# pov.net
KiCad netlist of a schematic drawn in EAGLE
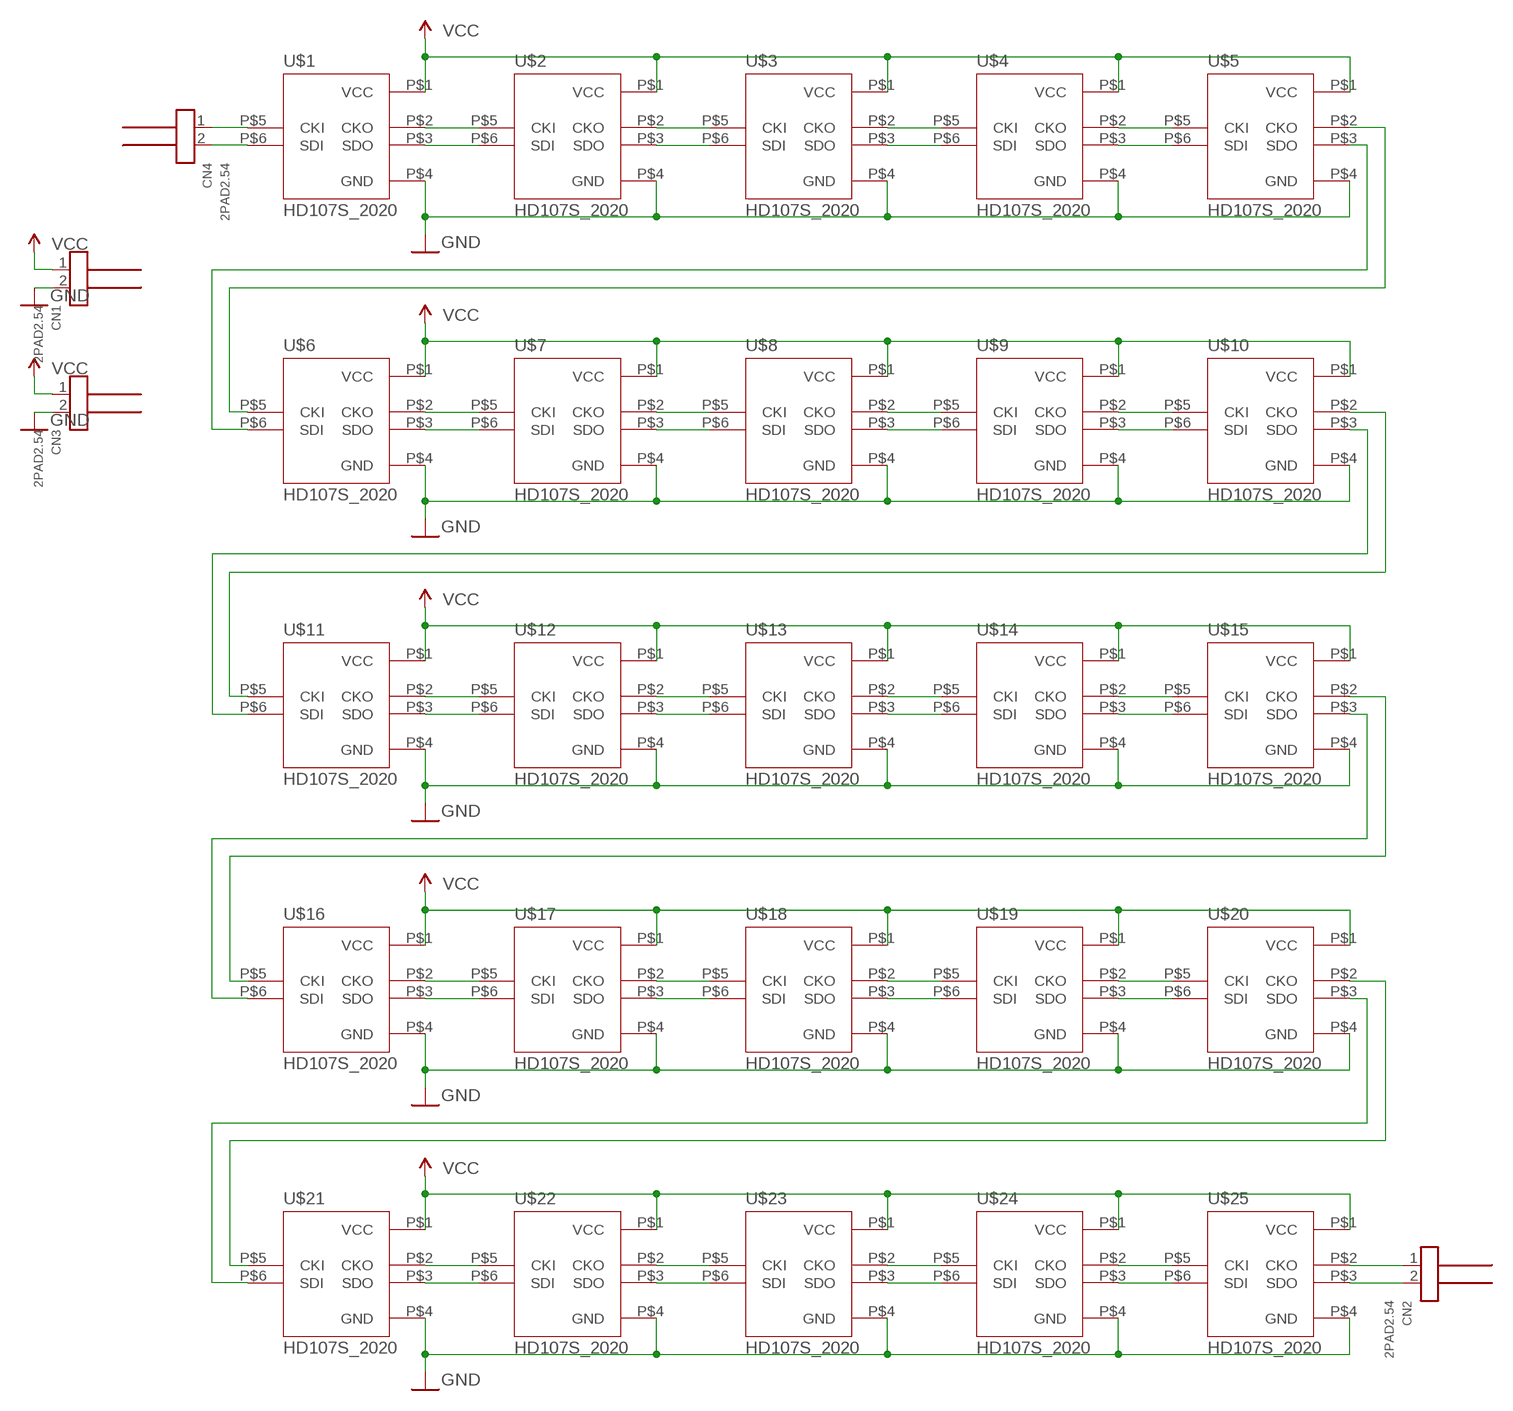
[diagram p0: schematic, sheet 1]

(export (version "E")
  (design (tool "Eeschema 10.0.6"))
  (components
    (comp (ref "CN1")
      (value "2PAD2.54")
      (footprint "eagle-import:2POLE_P2.54")
      (libsource (lib "eagle-import") (part "2PAD2.54"))
    )
    (comp (ref "CN2")
      (value "2PAD2.54")
      (footprint "eagle-import:2POLE_P2.54")
      (libsource (lib "eagle-import") (part "2PAD2.54"))
    )
    (comp (ref "CN3")
      (value "2PAD2.54")
      (footprint "eagle-import:2POLE_P2.54")
      (libsource (lib "eagle-import") (part "2PAD2.54"))
    )
    (comp (ref "CN4")
      (value "2PAD2.54")
      (footprint "eagle-import:2POLE_P2.54")
      (libsource (lib "eagle-import") (part "2PAD2.54"))
    )
    (comp (ref "U$1")
      (value "HD107S_2020")
      (footprint "eagle-import:HD107S_2020_FOOTPRINT")
      (libsource (lib "eagle-import") (part "HD107S_2020"))
    )
    (comp (ref "U$2")
      (value "HD107S_2020")
      (footprint "eagle-import:HD107S_2020_FOOTPRINT")
      (libsource (lib "eagle-import") (part "HD107S_2020"))
    )
    (comp (ref "U$3")
      (value "HD107S_2020")
      (footprint "eagle-import:HD107S_2020_FOOTPRINT")
      (libsource (lib "eagle-import") (part "HD107S_2020"))
    )
    (comp (ref "U$4")
      (value "HD107S_2020")
      (footprint "eagle-import:HD107S_2020_FOOTPRINT")
      (libsource (lib "eagle-import") (part "HD107S_2020"))
    )
    (comp (ref "U$5")
      (value "HD107S_2020")
      (footprint "eagle-import:HD107S_2020_FOOTPRINT")
      (libsource (lib "eagle-import") (part "HD107S_2020"))
    )
    (comp (ref "U$6")
      (value "HD107S_2020")
      (footprint "eagle-import:HD107S_2020_FOOTPRINT")
      (libsource (lib "eagle-import") (part "HD107S_2020"))
    )
    (comp (ref "U$7")
      (value "HD107S_2020")
      (footprint "eagle-import:HD107S_2020_FOOTPRINT")
      (libsource (lib "eagle-import") (part "HD107S_2020"))
    )
    (comp (ref "U$8")
      (value "HD107S_2020")
      (footprint "eagle-import:HD107S_2020_FOOTPRINT")
      (libsource (lib "eagle-import") (part "HD107S_2020"))
    )
    (comp (ref "U$9")
      (value "HD107S_2020")
      (footprint "eagle-import:HD107S_2020_FOOTPRINT")
      (libsource (lib "eagle-import") (part "HD107S_2020"))
    )
    (comp (ref "U$10")
      (value "HD107S_2020")
      (footprint "eagle-import:HD107S_2020_FOOTPRINT")
      (libsource (lib "eagle-import") (part "HD107S_2020"))
    )
    (comp (ref "U$11")
      (value "HD107S_2020")
      (footprint "eagle-import:HD107S_2020_FOOTPRINT")
      (libsource (lib "eagle-import") (part "HD107S_2020"))
    )
    (comp (ref "U$12")
      (value "HD107S_2020")
      (footprint "eagle-import:HD107S_2020_FOOTPRINT")
      (libsource (lib "eagle-import") (part "HD107S_2020"))
    )
    (comp (ref "U$13")
      (value "HD107S_2020")
      (footprint "eagle-import:HD107S_2020_FOOTPRINT")
      (libsource (lib "eagle-import") (part "HD107S_2020"))
    )
    (comp (ref "U$14")
      (value "HD107S_2020")
      (footprint "eagle-import:HD107S_2020_FOOTPRINT")
      (libsource (lib "eagle-import") (part "HD107S_2020"))
    )
    (comp (ref "U$15")
      (value "HD107S_2020")
      (footprint "eagle-import:HD107S_2020_FOOTPRINT")
      (libsource (lib "eagle-import") (part "HD107S_2020"))
    )
    (comp (ref "U$16")
      (value "HD107S_2020")
      (footprint "eagle-import:HD107S_2020_FOOTPRINT")
      (libsource (lib "eagle-import") (part "HD107S_2020"))
    )
    (comp (ref "U$17")
      (value "HD107S_2020")
      (footprint "eagle-import:HD107S_2020_FOOTPRINT")
      (libsource (lib "eagle-import") (part "HD107S_2020"))
    )
    (comp (ref "U$18")
      (value "HD107S_2020")
      (footprint "eagle-import:HD107S_2020_FOOTPRINT")
      (libsource (lib "eagle-import") (part "HD107S_2020"))
    )
    (comp (ref "U$19")
      (value "HD107S_2020")
      (footprint "eagle-import:HD107S_2020_FOOTPRINT")
      (libsource (lib "eagle-import") (part "HD107S_2020"))
    )
    (comp (ref "U$20")
      (value "HD107S_2020")
      (footprint "eagle-import:HD107S_2020_FOOTPRINT")
      (libsource (lib "eagle-import") (part "HD107S_2020"))
    )
    (comp (ref "U$21")
      (value "HD107S_2020")
      (footprint "eagle-import:HD107S_2020_FOOTPRINT")
      (libsource (lib "eagle-import") (part "HD107S_2020"))
    )
    (comp (ref "U$22")
      (value "HD107S_2020")
      (footprint "eagle-import:HD107S_2020_FOOTPRINT")
      (libsource (lib "eagle-import") (part "HD107S_2020"))
    )
    (comp (ref "U$23")
      (value "HD107S_2020")
      (footprint "eagle-import:HD107S_2020_FOOTPRINT")
      (libsource (lib "eagle-import") (part "HD107S_2020"))
    )
    (comp (ref "U$24")
      (value "HD107S_2020")
      (footprint "eagle-import:HD107S_2020_FOOTPRINT")
      (libsource (lib "eagle-import") (part "HD107S_2020"))
    )
    (comp (ref "U$25")
      (value "HD107S_2020")
      (footprint "eagle-import:HD107S_2020_FOOTPRINT")
      (libsource (lib "eagle-import") (part "HD107S_2020"))
    )
  )
  (nets
    (net (code "1") (name "GND") (class "Default")
      (node (ref "CN1") (pin "2") (pinfunction "P$2_2") (pintype "bidirectional"))
      (node (ref "CN3") (pin "2") (pinfunction "P$2_2") (pintype "bidirectional"))
      (node (ref "U$1") (pin "P$4") (pinfunction "GND_P$4") (pintype "bidirectional"))
      (node (ref "U$10") (pin "P$4") (pinfunction "GND_P$4") (pintype "bidirectional"))
      (node (ref "U$11") (pin "P$4") (pinfunction "GND_P$4") (pintype "bidirectional"))
      (node (ref "U$12") (pin "P$4") (pinfunction "GND_P$4") (pintype "bidirectional"))
      (node (ref "U$13") (pin "P$4") (pinfunction "GND_P$4") (pintype "bidirectional"))
      (node (ref "U$14") (pin "P$4") (pinfunction "GND_P$4") (pintype "bidirectional"))
      (node (ref "U$15") (pin "P$4") (pinfunction "GND_P$4") (pintype "bidirectional"))
      (node (ref "U$16") (pin "P$4") (pinfunction "GND_P$4") (pintype "bidirectional"))
      (node (ref "U$17") (pin "P$4") (pinfunction "GND_P$4") (pintype "bidirectional"))
      (node (ref "U$18") (pin "P$4") (pinfunction "GND_P$4") (pintype "bidirectional"))
      (node (ref "U$19") (pin "P$4") (pinfunction "GND_P$4") (pintype "bidirectional"))
      (node (ref "U$2") (pin "P$4") (pinfunction "GND_P$4") (pintype "bidirectional"))
      (node (ref "U$20") (pin "P$4") (pinfunction "GND_P$4") (pintype "bidirectional"))
      (node (ref "U$21") (pin "P$4") (pinfunction "GND_P$4") (pintype "bidirectional"))
      (node (ref "U$22") (pin "P$4") (pinfunction "GND_P$4") (pintype "bidirectional"))
      (node (ref "U$23") (pin "P$4") (pinfunction "GND_P$4") (pintype "bidirectional"))
      (node (ref "U$24") (pin "P$4") (pinfunction "GND_P$4") (pintype "bidirectional"))
      (node (ref "U$25") (pin "P$4") (pinfunction "GND_P$4") (pintype "bidirectional"))
      (node (ref "U$3") (pin "P$4") (pinfunction "GND_P$4") (pintype "bidirectional"))
      (node (ref "U$4") (pin "P$4") (pinfunction "GND_P$4") (pintype "bidirectional"))
      (node (ref "U$5") (pin "P$4") (pinfunction "GND_P$4") (pintype "bidirectional"))
      (node (ref "U$6") (pin "P$4") (pinfunction "GND_P$4") (pintype "bidirectional"))
      (node (ref "U$7") (pin "P$4") (pinfunction "GND_P$4") (pintype "bidirectional"))
      (node (ref "U$8") (pin "P$4") (pinfunction "GND_P$4") (pintype "bidirectional"))
      (node (ref "U$9") (pin "P$4") (pinfunction "GND_P$4") (pintype "bidirectional"))
    )
    (net (code "2") (name "Net-(CN2-P$1)") (class "Default")
      (node (ref "CN2") (pin "1") (pinfunction "P$1_1") (pintype "bidirectional"))
      (node (ref "U$25") (pin "P$2") (pinfunction "CKO_P$2") (pintype "bidirectional"))
    )
    (net (code "3") (name "Net-(CN2-P$2)") (class "Default")
      (node (ref "CN2") (pin "2") (pinfunction "P$2_2") (pintype "bidirectional"))
      (node (ref "U$25") (pin "P$3") (pinfunction "SDO_P$3") (pintype "bidirectional"))
    )
    (net (code "4") (name "Net-(CN4-P$1)") (class "Default")
      (node (ref "CN4") (pin "1") (pinfunction "P$1_1") (pintype "bidirectional"))
      (node (ref "U$1") (pin "P$5") (pinfunction "CKI_P$5") (pintype "bidirectional"))
    )
    (net (code "5") (name "Net-(CN4-P$2)") (class "Default")
      (node (ref "CN4") (pin "2") (pinfunction "P$2_2") (pintype "bidirectional"))
      (node (ref "U$1") (pin "P$6") (pinfunction "SDI_P$6") (pintype "bidirectional"))
    )
    (net (code "6") (name "Net-(U$1-CKO)") (class "Default")
      (node (ref "U$1") (pin "P$2") (pinfunction "CKO_P$2") (pintype "bidirectional"))
      (node (ref "U$2") (pin "P$5") (pinfunction "CKI_P$5") (pintype "bidirectional"))
    )
    (net (code "7") (name "Net-(U$1-SDO)") (class "Default")
      (node (ref "U$1") (pin "P$3") (pinfunction "SDO_P$3") (pintype "bidirectional"))
      (node (ref "U$2") (pin "P$6") (pinfunction "SDI_P$6") (pintype "bidirectional"))
    )
    (net (code "8") (name "Net-(U$2-CKO)") (class "Default")
      (node (ref "U$2") (pin "P$2") (pinfunction "CKO_P$2") (pintype "bidirectional"))
      (node (ref "U$3") (pin "P$5") (pinfunction "CKI_P$5") (pintype "bidirectional"))
    )
    (net (code "9") (name "Net-(U$2-SDO)") (class "Default")
      (node (ref "U$2") (pin "P$3") (pinfunction "SDO_P$3") (pintype "bidirectional"))
      (node (ref "U$3") (pin "P$6") (pinfunction "SDI_P$6") (pintype "bidirectional"))
    )
    (net (code "10") (name "Net-(U$3-CKO)") (class "Default")
      (node (ref "U$3") (pin "P$2") (pinfunction "CKO_P$2") (pintype "bidirectional"))
      (node (ref "U$4") (pin "P$5") (pinfunction "CKI_P$5") (pintype "bidirectional"))
    )
    (net (code "11") (name "Net-(U$3-SDO)") (class "Default")
      (node (ref "U$3") (pin "P$3") (pinfunction "SDO_P$3") (pintype "bidirectional"))
      (node (ref "U$4") (pin "P$6") (pinfunction "SDI_P$6") (pintype "bidirectional"))
    )
    (net (code "12") (name "Net-(U$4-CKO)") (class "Default")
      (node (ref "U$4") (pin "P$2") (pinfunction "CKO_P$2") (pintype "bidirectional"))
      (node (ref "U$5") (pin "P$5") (pinfunction "CKI_P$5") (pintype "bidirectional"))
    )
    (net (code "13") (name "Net-(U$4-SDO)") (class "Default")
      (node (ref "U$4") (pin "P$3") (pinfunction "SDO_P$3") (pintype "bidirectional"))
      (node (ref "U$5") (pin "P$6") (pinfunction "SDI_P$6") (pintype "bidirectional"))
    )
    (net (code "14") (name "Net-(U$5-CKO)") (class "Default")
      (node (ref "U$5") (pin "P$2") (pinfunction "CKO_P$2") (pintype "bidirectional"))
      (node (ref "U$6") (pin "P$5") (pinfunction "CKI_P$5") (pintype "bidirectional"))
    )
    (net (code "15") (name "Net-(U$5-SDO)") (class "Default")
      (node (ref "U$5") (pin "P$3") (pinfunction "SDO_P$3") (pintype "bidirectional"))
      (node (ref "U$6") (pin "P$6") (pinfunction "SDI_P$6") (pintype "bidirectional"))
    )
    (net (code "16") (name "Net-(U$6-CKO)") (class "Default")
      (node (ref "U$6") (pin "P$2") (pinfunction "CKO_P$2") (pintype "bidirectional"))
      (node (ref "U$7") (pin "P$5") (pinfunction "CKI_P$5") (pintype "bidirectional"))
    )
    (net (code "17") (name "Net-(U$6-SDO)") (class "Default")
      (node (ref "U$6") (pin "P$3") (pinfunction "SDO_P$3") (pintype "bidirectional"))
      (node (ref "U$7") (pin "P$6") (pinfunction "SDI_P$6") (pintype "bidirectional"))
    )
    (net (code "18") (name "Net-(U$7-CKO)") (class "Default")
      (node (ref "U$7") (pin "P$2") (pinfunction "CKO_P$2") (pintype "bidirectional"))
      (node (ref "U$8") (pin "P$5") (pinfunction "CKI_P$5") (pintype "bidirectional"))
    )
    (net (code "19") (name "Net-(U$7-SDO)") (class "Default")
      (node (ref "U$7") (pin "P$3") (pinfunction "SDO_P$3") (pintype "bidirectional"))
      (node (ref "U$8") (pin "P$6") (pinfunction "SDI_P$6") (pintype "bidirectional"))
    )
    (net (code "20") (name "Net-(U$8-CKO)") (class "Default")
      (node (ref "U$8") (pin "P$2") (pinfunction "CKO_P$2") (pintype "bidirectional"))
      (node (ref "U$9") (pin "P$5") (pinfunction "CKI_P$5") (pintype "bidirectional"))
    )
    (net (code "21") (name "Net-(U$8-SDO)") (class "Default")
      (node (ref "U$8") (pin "P$3") (pinfunction "SDO_P$3") (pintype "bidirectional"))
      (node (ref "U$9") (pin "P$6") (pinfunction "SDI_P$6") (pintype "bidirectional"))
    )
    (net (code "22") (name "Net-(U$10-CKI)") (class "Default")
      (node (ref "U$10") (pin "P$5") (pinfunction "CKI_P$5") (pintype "bidirectional"))
      (node (ref "U$9") (pin "P$2") (pinfunction "CKO_P$2") (pintype "bidirectional"))
    )
    (net (code "23") (name "Net-(U$10-CKO)") (class "Default")
      (node (ref "U$10") (pin "P$2") (pinfunction "CKO_P$2") (pintype "bidirectional"))
      (node (ref "U$11") (pin "P$5") (pinfunction "CKI_P$5") (pintype "bidirectional"))
    )
    (net (code "24") (name "Net-(U$10-SDI)") (class "Default")
      (node (ref "U$10") (pin "P$6") (pinfunction "SDI_P$6") (pintype "bidirectional"))
      (node (ref "U$9") (pin "P$3") (pinfunction "SDO_P$3") (pintype "bidirectional"))
    )
    (net (code "25") (name "Net-(U$10-SDO)") (class "Default")
      (node (ref "U$10") (pin "P$3") (pinfunction "SDO_P$3") (pintype "bidirectional"))
      (node (ref "U$11") (pin "P$6") (pinfunction "SDI_P$6") (pintype "bidirectional"))
    )
    (net (code "26") (name "Net-(U$11-CKO)") (class "Default")
      (node (ref "U$11") (pin "P$2") (pinfunction "CKO_P$2") (pintype "bidirectional"))
      (node (ref "U$12") (pin "P$5") (pinfunction "CKI_P$5") (pintype "bidirectional"))
    )
    (net (code "27") (name "Net-(U$11-SDO)") (class "Default")
      (node (ref "U$11") (pin "P$3") (pinfunction "SDO_P$3") (pintype "bidirectional"))
      (node (ref "U$12") (pin "P$6") (pinfunction "SDI_P$6") (pintype "bidirectional"))
    )
    (net (code "28") (name "Net-(U$12-CKO)") (class "Default")
      (node (ref "U$12") (pin "P$2") (pinfunction "CKO_P$2") (pintype "bidirectional"))
      (node (ref "U$13") (pin "P$5") (pinfunction "CKI_P$5") (pintype "bidirectional"))
    )
    (net (code "29") (name "Net-(U$12-SDO)") (class "Default")
      (node (ref "U$12") (pin "P$3") (pinfunction "SDO_P$3") (pintype "bidirectional"))
      (node (ref "U$13") (pin "P$6") (pinfunction "SDI_P$6") (pintype "bidirectional"))
    )
    (net (code "30") (name "Net-(U$13-CKO)") (class "Default")
      (node (ref "U$13") (pin "P$2") (pinfunction "CKO_P$2") (pintype "bidirectional"))
      (node (ref "U$14") (pin "P$5") (pinfunction "CKI_P$5") (pintype "bidirectional"))
    )
    (net (code "31") (name "Net-(U$13-SDO)") (class "Default")
      (node (ref "U$13") (pin "P$3") (pinfunction "SDO_P$3") (pintype "bidirectional"))
      (node (ref "U$14") (pin "P$6") (pinfunction "SDI_P$6") (pintype "bidirectional"))
    )
    (net (code "32") (name "Net-(U$14-CKO)") (class "Default")
      (node (ref "U$14") (pin "P$2") (pinfunction "CKO_P$2") (pintype "bidirectional"))
      (node (ref "U$15") (pin "P$5") (pinfunction "CKI_P$5") (pintype "bidirectional"))
    )
    (net (code "33") (name "Net-(U$14-SDO)") (class "Default")
      (node (ref "U$14") (pin "P$3") (pinfunction "SDO_P$3") (pintype "bidirectional"))
      (node (ref "U$15") (pin "P$6") (pinfunction "SDI_P$6") (pintype "bidirectional"))
    )
    (net (code "34") (name "Net-(U$15-CKO)") (class "Default")
      (node (ref "U$15") (pin "P$2") (pinfunction "CKO_P$2") (pintype "bidirectional"))
      (node (ref "U$16") (pin "P$5") (pinfunction "CKI_P$5") (pintype "bidirectional"))
    )
    (net (code "35") (name "Net-(U$15-SDO)") (class "Default")
      (node (ref "U$15") (pin "P$3") (pinfunction "SDO_P$3") (pintype "bidirectional"))
      (node (ref "U$16") (pin "P$6") (pinfunction "SDI_P$6") (pintype "bidirectional"))
    )
    (net (code "36") (name "Net-(U$16-CKO)") (class "Default")
      (node (ref "U$16") (pin "P$2") (pinfunction "CKO_P$2") (pintype "bidirectional"))
      (node (ref "U$17") (pin "P$5") (pinfunction "CKI_P$5") (pintype "bidirectional"))
    )
    (net (code "37") (name "Net-(U$16-SDO)") (class "Default")
      (node (ref "U$16") (pin "P$3") (pinfunction "SDO_P$3") (pintype "bidirectional"))
      (node (ref "U$17") (pin "P$6") (pinfunction "SDI_P$6") (pintype "bidirectional"))
    )
    (net (code "38") (name "Net-(U$17-CKO)") (class "Default")
      (node (ref "U$17") (pin "P$2") (pinfunction "CKO_P$2") (pintype "bidirectional"))
      (node (ref "U$18") (pin "P$5") (pinfunction "CKI_P$5") (pintype "bidirectional"))
    )
    (net (code "39") (name "Net-(U$17-SDO)") (class "Default")
      (node (ref "U$17") (pin "P$3") (pinfunction "SDO_P$3") (pintype "bidirectional"))
      (node (ref "U$18") (pin "P$6") (pinfunction "SDI_P$6") (pintype "bidirectional"))
    )
    (net (code "40") (name "Net-(U$18-CKO)") (class "Default")
      (node (ref "U$18") (pin "P$2") (pinfunction "CKO_P$2") (pintype "bidirectional"))
      (node (ref "U$19") (pin "P$5") (pinfunction "CKI_P$5") (pintype "bidirectional"))
    )
    (net (code "41") (name "Net-(U$18-SDO)") (class "Default")
      (node (ref "U$18") (pin "P$3") (pinfunction "SDO_P$3") (pintype "bidirectional"))
      (node (ref "U$19") (pin "P$6") (pinfunction "SDI_P$6") (pintype "bidirectional"))
    )
    (net (code "42") (name "Net-(U$19-CKO)") (class "Default")
      (node (ref "U$19") (pin "P$2") (pinfunction "CKO_P$2") (pintype "bidirectional"))
      (node (ref "U$20") (pin "P$5") (pinfunction "CKI_P$5") (pintype "bidirectional"))
    )
    (net (code "43") (name "Net-(U$19-SDO)") (class "Default")
      (node (ref "U$19") (pin "P$3") (pinfunction "SDO_P$3") (pintype "bidirectional"))
      (node (ref "U$20") (pin "P$6") (pinfunction "SDI_P$6") (pintype "bidirectional"))
    )
    (net (code "44") (name "Net-(U$20-CKO)") (class "Default")
      (node (ref "U$20") (pin "P$2") (pinfunction "CKO_P$2") (pintype "bidirectional"))
      (node (ref "U$21") (pin "P$5") (pinfunction "CKI_P$5") (pintype "bidirectional"))
    )
    (net (code "45") (name "Net-(U$20-SDO)") (class "Default")
      (node (ref "U$20") (pin "P$3") (pinfunction "SDO_P$3") (pintype "bidirectional"))
      (node (ref "U$21") (pin "P$6") (pinfunction "SDI_P$6") (pintype "bidirectional"))
    )
    (net (code "46") (name "Net-(U$21-CKO)") (class "Default")
      (node (ref "U$21") (pin "P$2") (pinfunction "CKO_P$2") (pintype "bidirectional"))
      (node (ref "U$22") (pin "P$5") (pinfunction "CKI_P$5") (pintype "bidirectional"))
    )
    (net (code "47") (name "Net-(U$21-SDO)") (class "Default")
      (node (ref "U$21") (pin "P$3") (pinfunction "SDO_P$3") (pintype "bidirectional"))
      (node (ref "U$22") (pin "P$6") (pinfunction "SDI_P$6") (pintype "bidirectional"))
    )
    (net (code "48") (name "Net-(U$22-CKO)") (class "Default")
      (node (ref "U$22") (pin "P$2") (pinfunction "CKO_P$2") (pintype "bidirectional"))
      (node (ref "U$23") (pin "P$5") (pinfunction "CKI_P$5") (pintype "bidirectional"))
    )
    (net (code "49") (name "Net-(U$22-SDO)") (class "Default")
      (node (ref "U$22") (pin "P$3") (pinfunction "SDO_P$3") (pintype "bidirectional"))
      (node (ref "U$23") (pin "P$6") (pinfunction "SDI_P$6") (pintype "bidirectional"))
    )
    (net (code "50") (name "Net-(U$23-CKO)") (class "Default")
      (node (ref "U$23") (pin "P$2") (pinfunction "CKO_P$2") (pintype "bidirectional"))
      (node (ref "U$24") (pin "P$5") (pinfunction "CKI_P$5") (pintype "bidirectional"))
    )
    (net (code "51") (name "Net-(U$23-SDO)") (class "Default")
      (node (ref "U$23") (pin "P$3") (pinfunction "SDO_P$3") (pintype "bidirectional"))
      (node (ref "U$24") (pin "P$6") (pinfunction "SDI_P$6") (pintype "bidirectional"))
    )
    (net (code "52") (name "Net-(U$24-CKO)") (class "Default")
      (node (ref "U$24") (pin "P$2") (pinfunction "CKO_P$2") (pintype "bidirectional"))
      (node (ref "U$25") (pin "P$5") (pinfunction "CKI_P$5") (pintype "bidirectional"))
    )
    (net (code "53") (name "Net-(U$24-SDO)") (class "Default")
      (node (ref "U$24") (pin "P$3") (pinfunction "SDO_P$3") (pintype "bidirectional"))
      (node (ref "U$25") (pin "P$6") (pinfunction "SDI_P$6") (pintype "bidirectional"))
    )
    (net (code "54") (name "VCC") (class "Default")
      (node (ref "CN1") (pin "1") (pinfunction "P$1_1") (pintype "bidirectional"))
      (node (ref "CN3") (pin "1") (pinfunction "P$1_1") (pintype "bidirectional"))
      (node (ref "U$1") (pin "P$1") (pinfunction "VCC_P$1") (pintype "bidirectional"))
      (node (ref "U$10") (pin "P$1") (pinfunction "VCC_P$1") (pintype "bidirectional"))
      (node (ref "U$11") (pin "P$1") (pinfunction "VCC_P$1") (pintype "bidirectional"))
      (node (ref "U$12") (pin "P$1") (pinfunction "VCC_P$1") (pintype "bidirectional"))
      (node (ref "U$13") (pin "P$1") (pinfunction "VCC_P$1") (pintype "bidirectional"))
      (node (ref "U$14") (pin "P$1") (pinfunction "VCC_P$1") (pintype "bidirectional"))
      (node (ref "U$15") (pin "P$1") (pinfunction "VCC_P$1") (pintype "bidirectional"))
      (node (ref "U$16") (pin "P$1") (pinfunction "VCC_P$1") (pintype "bidirectional"))
      (node (ref "U$17") (pin "P$1") (pinfunction "VCC_P$1") (pintype "bidirectional"))
      (node (ref "U$18") (pin "P$1") (pinfunction "VCC_P$1") (pintype "bidirectional"))
      (node (ref "U$19") (pin "P$1") (pinfunction "VCC_P$1") (pintype "bidirectional"))
      (node (ref "U$2") (pin "P$1") (pinfunction "VCC_P$1") (pintype "bidirectional"))
      (node (ref "U$20") (pin "P$1") (pinfunction "VCC_P$1") (pintype "bidirectional"))
      (node (ref "U$21") (pin "P$1") (pinfunction "VCC_P$1") (pintype "bidirectional"))
      (node (ref "U$22") (pin "P$1") (pinfunction "VCC_P$1") (pintype "bidirectional"))
      (node (ref "U$23") (pin "P$1") (pinfunction "VCC_P$1") (pintype "bidirectional"))
      (node (ref "U$24") (pin "P$1") (pinfunction "VCC_P$1") (pintype "bidirectional"))
      (node (ref "U$25") (pin "P$1") (pinfunction "VCC_P$1") (pintype "bidirectional"))
      (node (ref "U$3") (pin "P$1") (pinfunction "VCC_P$1") (pintype "bidirectional"))
      (node (ref "U$4") (pin "P$1") (pinfunction "VCC_P$1") (pintype "bidirectional"))
      (node (ref "U$5") (pin "P$1") (pinfunction "VCC_P$1") (pintype "bidirectional"))
      (node (ref "U$6") (pin "P$1") (pinfunction "VCC_P$1") (pintype "bidirectional"))
      (node (ref "U$7") (pin "P$1") (pinfunction "VCC_P$1") (pintype "bidirectional"))
      (node (ref "U$8") (pin "P$1") (pinfunction "VCC_P$1") (pintype "bidirectional"))
      (node (ref "U$9") (pin "P$1") (pinfunction "VCC_P$1") (pintype "bidirectional"))
    )
  )
)
